# PSU_CLASS_AB.net
KiCad netlist of a schematic drawn in EAGLE
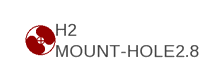
[diagram p0: schematic, sheet 1, part 1 of 2]
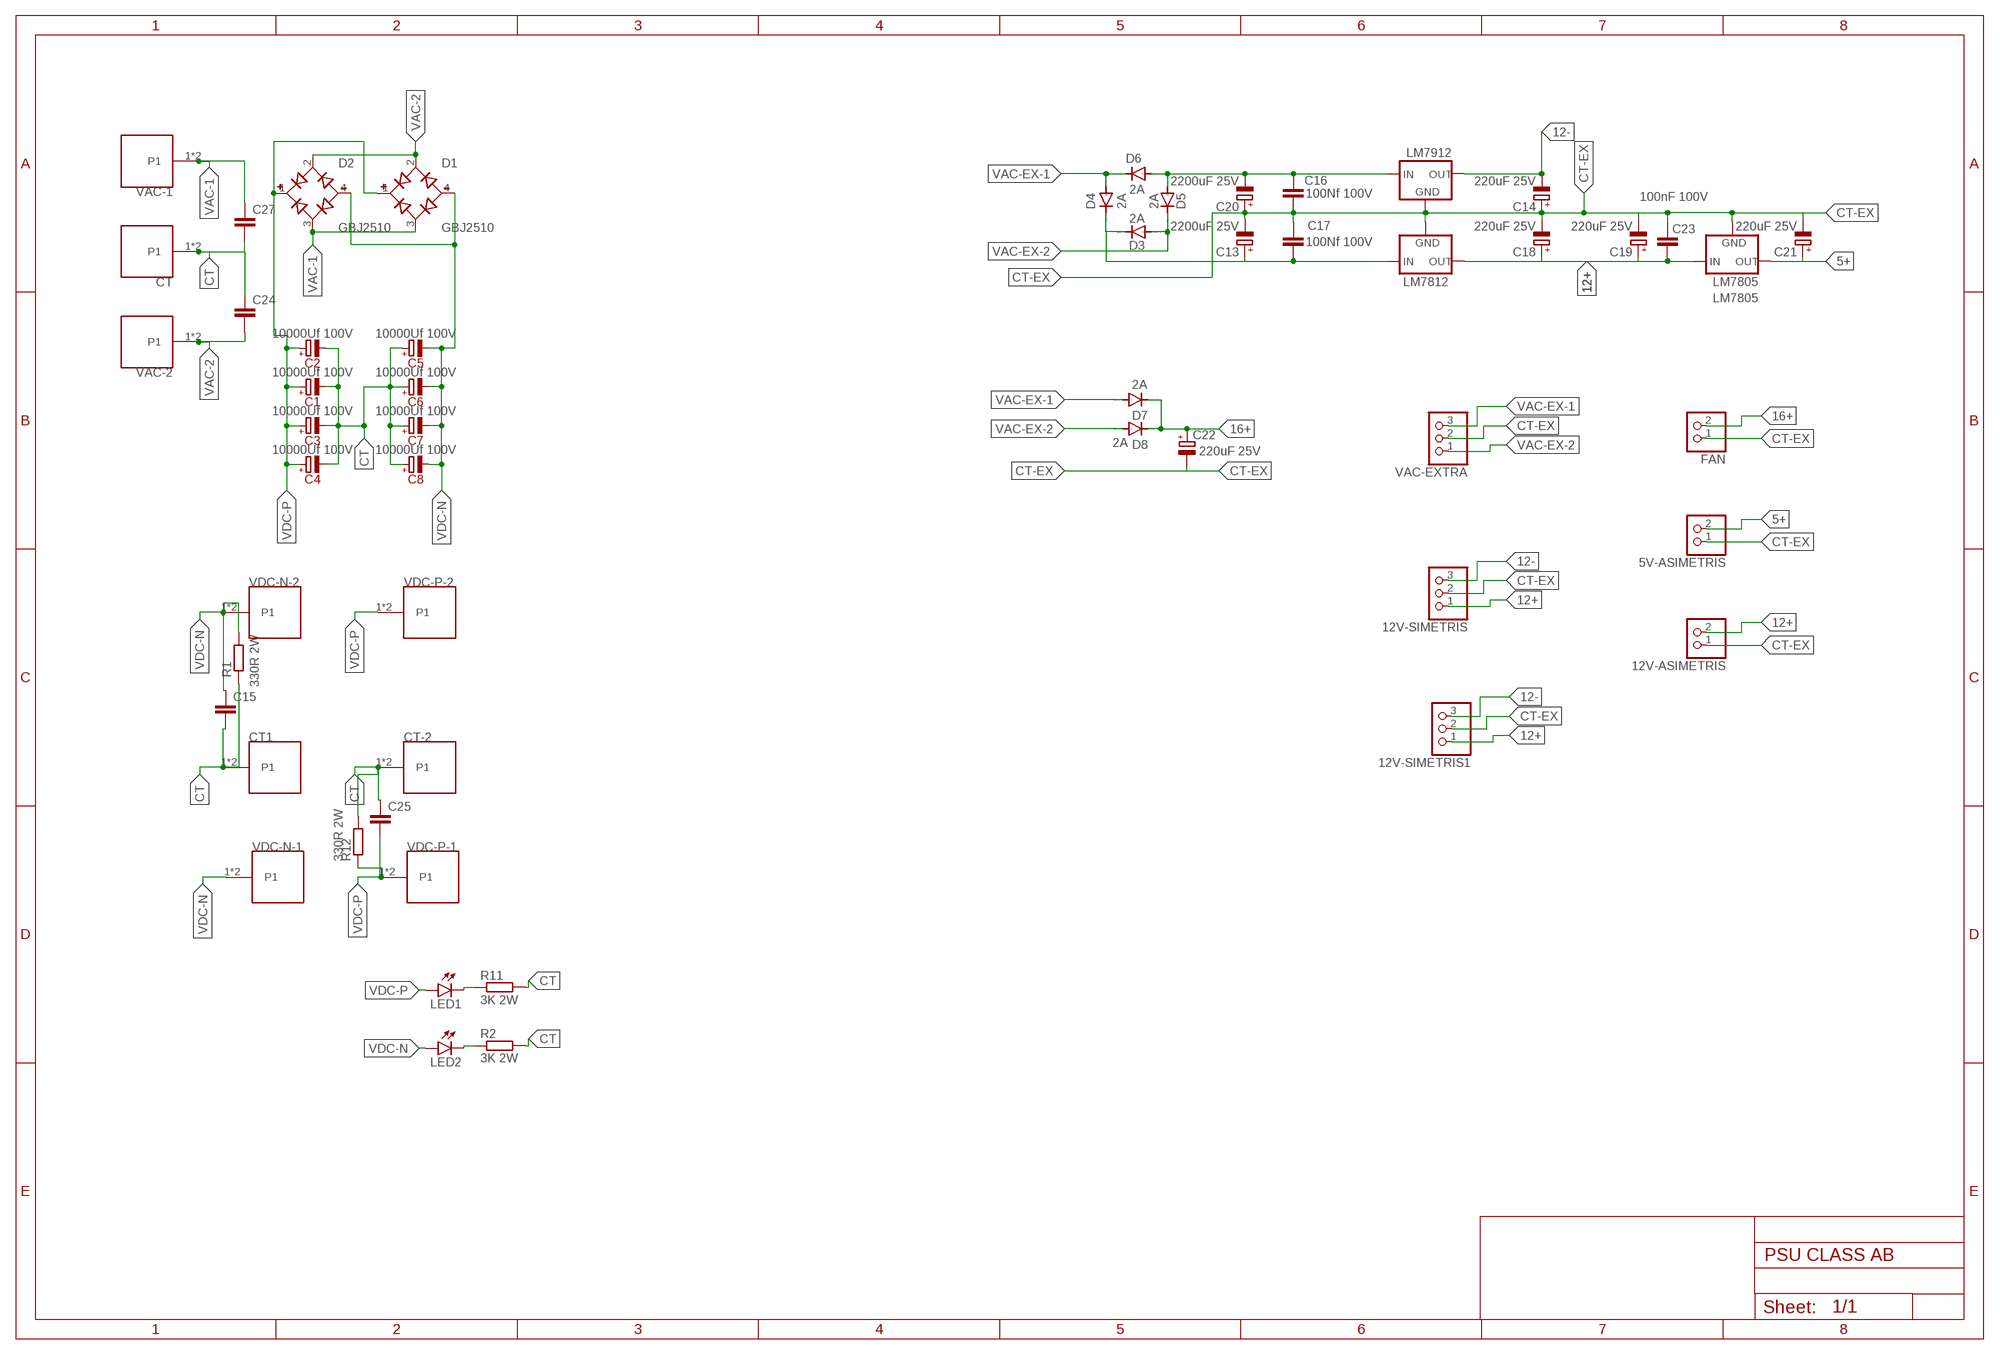
[diagram p1: schematic, sheet 1, part 2 of 2]

(export (version "E")
  (design (tool "Eeschema 10.0.6"))
  (components
    (comp (ref "5V-ASIMETRIS")
      (value "PINHD-1X2")
      (footprint "eagle-import:1X02")
      (libsource (lib "eagle-import") (part "PINHD-1X2"))
    )
    (comp (ref "12V-ASIMETRIS")
      (value "PINHD-1X2")
      (footprint "eagle-import:1X02")
      (libsource (lib "eagle-import") (part "PINHD-1X2"))
    )
    (comp (ref "12V-SIMETRIS")
      (value "PINHD-1X3")
      (footprint "eagle-import:1X03")
      (libsource (lib "eagle-import") (part "PINHD-1X3"))
    )
    (comp (ref "12V-SIMETRIS1")
      (value "PINHD-1X3")
      (footprint "eagle-import:1X03")
      (libsource (lib "eagle-import") (part "PINHD-1X3"))
    )
    (comp (ref "C1")
      (value "10000Uf 100V")
      (footprint "eagle-import:E1,5-4")
      (libsource (lib "eagle-import") (part "?1U/50V"))
    )
    (comp (ref "C2")
      (value "10000Uf 100V")
      (footprint "eagle-import:E1,5-4")
      (libsource (lib "eagle-import") (part "?1U/50V"))
    )
    (comp (ref "C3")
      (value "10000Uf 100V")
      (footprint "eagle-import:E1,5-4")
      (libsource (lib "eagle-import") (part "?1U/50V"))
    )
    (comp (ref "C4")
      (value "10000Uf 100V")
      (footprint "eagle-import:E1,5-4")
      (libsource (lib "eagle-import") (part "?1U/50V"))
    )
    (comp (ref "C5")
      (value "10000Uf 100V")
      (footprint "eagle-import:E1,5-4")
      (libsource (lib "eagle-import") (part "?1U/50V"))
    )
    (comp (ref "C6")
      (value "10000Uf 100V")
      (footprint "eagle-import:E1,5-4")
      (libsource (lib "eagle-import") (part "?1U/50V"))
    )
    (comp (ref "C7")
      (value "10000Uf 100V")
      (footprint "eagle-import:E1,5-4")
      (libsource (lib "eagle-import") (part "?1U/50V"))
    )
    (comp (ref "C8")
      (value "10000Uf 100V")
      (footprint "eagle-import:E1,5-4")
      (libsource (lib "eagle-import") (part "?1U/50V"))
    )
    (comp (ref "C13")
      (value "2200uF 25V")
      (footprint "eagle-import:E3,5-8")
      (libsource (lib "eagle-import") (part "CPOL-EUE3.5-8"))
    )
    (comp (ref "C14")
      (value "220uF 25V")
      (footprint "eagle-import:E3,5-8")
      (libsource (lib "eagle-import") (part "CPOL-EUE3.5-8"))
    )
    (comp (ref "C15")
      (value "C10/5")
      (footprint "eagle-import:C10B5")
      (libsource (lib "eagle-import") (part "capacitor-wima_116_C10/5"))
    )
    (comp (ref "C16")
      (value "100Nf 100V")
      (footprint "eagle-import:C5B3")
      (libsource (lib "eagle-import") (part "C5/3"))
    )
    (comp (ref "C17")
      (value "100Nf 100V")
      (footprint "eagle-import:C5B3")
      (libsource (lib "eagle-import") (part "C5/3"))
    )
    (comp (ref "C18")
      (value "220uF 25V")
      (footprint "eagle-import:E3,5-8")
      (libsource (lib "eagle-import") (part "CPOL-EUE3.5-8"))
    )
    (comp (ref "C19")
      (value "220uF 25V")
      (footprint "eagle-import:E3,5-8")
      (libsource (lib "eagle-import") (part "CPOL-EUE3.5-8"))
    )
    (comp (ref "C20")
      (value "2200uF 25V")
      (footprint "eagle-import:E3,5-8")
      (libsource (lib "eagle-import") (part "CPOL-EUE3.5-8"))
    )
    (comp (ref "C21")
      (value "220uF 25V")
      (footprint "eagle-import:E3,5-8")
      (libsource (lib "eagle-import") (part "CPOL-EUE3.5-8"))
    )
    (comp (ref "C22")
      (value "220uF 25V")
      (footprint "eagle-import:E3,5-8")
      (libsource (lib "eagle-import") (part "CPOL-EUE3.5-8"))
    )
    (comp (ref "C23")
      (value "100nF 100V")
      (footprint "eagle-import:C5B3")
      (libsource (lib "eagle-import") (part "C5/3"))
    )
    (comp (ref "C24")
      (value "C10/5")
      (footprint "eagle-import:C10B5")
      (libsource (lib "eagle-import") (part "capacitor-wima_116_C10/5"))
    )
    (comp (ref "C25")
      (value "C10/5")
      (footprint "eagle-import:C10B5")
      (libsource (lib "eagle-import") (part "capacitor-wima_116_C10/5"))
    )
    (comp (ref "C27")
      (value "C10/5")
      (footprint "eagle-import:C10B5")
      (libsource (lib "eagle-import") (part "capacitor-wima_116_C10/5"))
    )
    (comp (ref "CT")
      (value "62409-1")
      (footprint "eagle-import:TE_62409-1")
      (fields (field (name "MF") "TE Connectivity"))
      (libsource (lib "eagle-import") (part "62409-1"))
    )
    (comp (ref "CT-2")
      (value "62409-1")
      (footprint "eagle-import:TE_62409-1")
      (fields (field (name "MF") "TE Connectivity"))
      (libsource (lib "eagle-import") (part "62409-1"))
    )
    (comp (ref "CT1")
      (value "62409-1")
      (footprint "eagle-import:TE_62409-1")
      (fields (field (name "MF") "TE Connectivity"))
      (libsource (lib "eagle-import") (part "62409-1"))
    )
    (comp (ref "D1")
      (value "GBJ2510")
      (footprint "eagle-import:DIOB_GBJ2510")
      (fields (field (name "MF") "Diodes Inc."))
      (libsource (lib "eagle-import") (part "GBJ2510"))
    )
    (comp (ref "D2")
      (value "GBJ2510")
      (footprint "eagle-import:DIOB_GBJ2510")
      (fields (field (name "MF") "Diodes Inc."))
      (libsource (lib "eagle-import") (part "GBJ2510"))
    )
    (comp (ref "D3")
      (value "2A")
      (footprint "eagle-import:DO41-10")
      (libsource (lib "eagle-import") (part "1N4933"))
    )
    (comp (ref "D4")
      (value "2A")
      (footprint "eagle-import:DO41-10")
      (libsource (lib "eagle-import") (part "1N4933"))
    )
    (comp (ref "D5")
      (value "2A")
      (footprint "eagle-import:DO41-10")
      (libsource (lib "eagle-import") (part "1N4933"))
    )
    (comp (ref "D6")
      (value "2A")
      (footprint "eagle-import:DO41-10")
      (libsource (lib "eagle-import") (part "1N4933"))
    )
    (comp (ref "D7")
      (value "2A")
      (footprint "eagle-import:DO41-10")
      (libsource (lib "eagle-import") (part "1N4933"))
    )
    (comp (ref "D8")
      (value "2A")
      (footprint "eagle-import:DO41-10")
      (libsource (lib "eagle-import") (part "1N4933"))
    )
    (comp (ref "FAN")
      (value "PINHD-1X2")
      (footprint "eagle-import:1X02")
      (libsource (lib "eagle-import") (part "PINHD-1X2"))
    )
    (comp (ref "H2")
      (value "MOUNT-HOLE2.8")
      (footprint "eagle-import:2,8")
      (libsource (lib "eagle-import") (part "MOUNT-HOLE2.8"))
    )
    (comp (ref "LED1")
      (value "LED3MM")
      (footprint "eagle-import:LED3MM")
      (libsource (lib "eagle-import") (part "LED3MM"))
    )
    (comp (ref "LED2")
      (value "LED3MM")
      (footprint "eagle-import:LED3MM")
      (libsource (lib "eagle-import") (part "LED3MM"))
    )
    (comp (ref "LM7805")
      (value "LM7805")
      (footprint "eagle-import:78XXS")
      (libsource (lib "eagle-import") (part "78XXS"))
    )
    (comp (ref "LM7812")
      (value "LM7812")
      (footprint "eagle-import:78XXS")
      (libsource (lib "eagle-import") (part "78XXS"))
    )
    (comp (ref "LM7912")
      (value "LM7912")
      (footprint "eagle-import:79XXS")
      (libsource (lib "eagle-import") (part "79XXS"))
    )
    (comp (ref "R1")
      (value "330R 2W")
      (footprint "eagle-import:0207_15")
      (libsource (lib "eagle-import") (part "R-EU_0207/15"))
    )
    (comp (ref "R2")
      (value "3K 2W")
      (footprint "eagle-import:0207_15")
      (libsource (lib "eagle-import") (part "R-EU_0207/15"))
    )
    (comp (ref "R11")
      (value "3K 2W")
      (footprint "eagle-import:0207_15")
      (libsource (lib "eagle-import") (part "R-EU_0207/15"))
    )
    (comp (ref "R12")
      (value "330R 2W")
      (footprint "eagle-import:0207_15")
      (libsource (lib "eagle-import") (part "R-EU_0207/15"))
    )
    (comp (ref "VAC-1")
      (value "62409-1")
      (footprint "eagle-import:TE_62409-1")
      (fields (field (name "MF") "TE Connectivity"))
      (libsource (lib "eagle-import") (part "62409-1"))
    )
    (comp (ref "VAC-2")
      (value "62409-1")
      (footprint "eagle-import:TE_62409-1")
      (fields (field (name "MF") "TE Connectivity"))
      (libsource (lib "eagle-import") (part "62409-1"))
    )
    (comp (ref "VAC-EXTRA")
      (value "PINHD-1X3")
      (footprint "eagle-import:1X03")
      (libsource (lib "eagle-import") (part "PINHD-1X3"))
    )
    (comp (ref "VDC-N-1")
      (value "62409-1")
      (footprint "eagle-import:TE_62409-1")
      (fields (field (name "MF") "TE Connectivity"))
      (libsource (lib "eagle-import") (part "62409-1"))
    )
    (comp (ref "VDC-N-2")
      (value "62409-1")
      (footprint "eagle-import:TE_62409-1")
      (fields (field (name "MF") "TE Connectivity"))
      (libsource (lib "eagle-import") (part "62409-1"))
    )
    (comp (ref "VDC-P-1")
      (value "62409-1")
      (footprint "eagle-import:TE_62409-1")
      (fields (field (name "MF") "TE Connectivity"))
      (libsource (lib "eagle-import") (part "62409-1"))
    )
    (comp (ref "VDC-P-2")
      (value "62409-1")
      (footprint "eagle-import:TE_62409-1")
      (fields (field (name "MF") "TE Connectivity"))
      (libsource (lib "eagle-import") (part "62409-1"))
    )
  )
  (nets
    (net (code "1") (name "5+") (class "Default")
      (node (ref "5V-ASIMETRIS") (pin "2") (pinfunction "2_2") (pintype "passive"))
      (node (ref "C21") (pin "+") (pinfunction "+_+") (pintype "passive"))
      (node (ref "LM7805") (pin "OUT") (pinfunction "OUT_OUT") (pintype "passive"))
    )
    (net (code "2") (name "12+") (class "Default")
      (node (ref "12V-ASIMETRIS") (pin "2") (pinfunction "2_2") (pintype "passive"))
      (node (ref "12V-SIMETRIS") (pin "1") (pinfunction "1_1") (pintype "passive"))
      (node (ref "12V-SIMETRIS1") (pin "1") (pinfunction "1_1") (pintype "passive"))
      (node (ref "C18") (pin "+") (pinfunction "+_+") (pintype "passive"))
      (node (ref "C19") (pin "+") (pinfunction "+_+") (pintype "passive"))
      (node (ref "C23") (pin "1") (pinfunction "1_1") (pintype "passive"))
      (node (ref "LM7805") (pin "IN") (pinfunction "IN_IN") (pintype "input"))
      (node (ref "LM7812") (pin "OUT") (pinfunction "OUT_OUT") (pintype "passive"))
    )
    (net (code "3") (name "12-") (class "Default")
      (node (ref "12V-SIMETRIS") (pin "3") (pinfunction "3_3") (pintype "passive"))
      (node (ref "12V-SIMETRIS1") (pin "3") (pinfunction "3_3") (pintype "passive"))
      (node (ref "C14") (pin "-") (pinfunction "-_-") (pintype "passive"))
      (node (ref "LM7912") (pin "OUT") (pinfunction "OUT_OUT") (pintype "passive"))
    )
    (net (code "4") (name "16+") (class "Default")
      (node (ref "C22") (pin "+") (pinfunction "+_+") (pintype "passive"))
      (node (ref "D7") (pin "C") (pinfunction "C_C") (pintype "passive"))
      (node (ref "D8") (pin "C") (pinfunction "C_C") (pintype "passive"))
      (node (ref "FAN") (pin "2") (pinfunction "2_2") (pintype "passive"))
    )
    (net (code "5") (name "CT") (class "Default")
      (node (ref "C1") (pin "-") (pinfunction "-_-") (pintype "passive"))
      (node (ref "C15") (pin "2") (pinfunction "2_2") (pintype "passive"))
      (node (ref "C2") (pin "-") (pinfunction "-_-") (pintype "passive"))
      (node (ref "C24") (pin "1") (pinfunction "1_1") (pintype "passive"))
      (node (ref "C25") (pin "1") (pinfunction "1_1") (pintype "passive"))
      (node (ref "C27") (pin "2") (pinfunction "2_2") (pintype "passive"))
      (node (ref "C3") (pin "-") (pinfunction "-_-") (pintype "passive"))
      (node (ref "C4") (pin "-") (pinfunction "-_-") (pintype "passive"))
      (node (ref "C5") (pin "+") (pinfunction "+_+") (pintype "passive"))
      (node (ref "C6") (pin "+") (pinfunction "+_+") (pintype "passive"))
      (node (ref "C7") (pin "+") (pinfunction "+_+") (pintype "passive"))
      (node (ref "C8") (pin "+") (pinfunction "+_+") (pintype "passive"))
      (node (ref "CT") (pin "1") (pinfunction "P1_1") (pintype "passive"))
      (node (ref "CT") (pin "2") (pinfunction "P1_2") (pintype "passive"))
      (node (ref "CT-2") (pin "1") (pinfunction "P1_1") (pintype "passive"))
      (node (ref "CT-2") (pin "2") (pinfunction "P1_2") (pintype "passive"))
      (node (ref "CT1") (pin "1") (pinfunction "P1_1") (pintype "passive"))
      (node (ref "CT1") (pin "2") (pinfunction "P1_2") (pintype "passive"))
      (node (ref "R1") (pin "1") (pinfunction "1_1") (pintype "passive"))
      (node (ref "R11") (pin "2") (pinfunction "2_2") (pintype "passive"))
      (node (ref "R12") (pin "2") (pinfunction "2_2") (pintype "passive"))
      (node (ref "R2") (pin "2") (pinfunction "2_2") (pintype "passive"))
    )
    (net (code "6") (name "CT-EX") (class "Default")
      (node (ref "12V-ASIMETRIS") (pin "1") (pinfunction "1_1") (pintype "passive"))
      (node (ref "12V-SIMETRIS") (pin "2") (pinfunction "2_2") (pintype "passive"))
      (node (ref "12V-SIMETRIS1") (pin "2") (pinfunction "2_2") (pintype "passive"))
      (node (ref "5V-ASIMETRIS") (pin "1") (pinfunction "1_1") (pintype "passive"))
      (node (ref "C13") (pin "-") (pinfunction "-_-") (pintype "passive"))
      (node (ref "C14") (pin "+") (pinfunction "+_+") (pintype "passive"))
      (node (ref "C16") (pin "1") (pinfunction "1_1") (pintype "passive"))
      (node (ref "C17") (pin "2") (pinfunction "2_2") (pintype "passive"))
      (node (ref "C18") (pin "-") (pinfunction "-_-") (pintype "passive"))
      (node (ref "C19") (pin "-") (pinfunction "-_-") (pintype "passive"))
      (node (ref "C20") (pin "+") (pinfunction "+_+") (pintype "passive"))
      (node (ref "C21") (pin "-") (pinfunction "-_-") (pintype "passive"))
      (node (ref "C22") (pin "-") (pinfunction "-_-") (pintype "passive"))
      (node (ref "C23") (pin "2") (pinfunction "2_2") (pintype "passive"))
      (node (ref "FAN") (pin "1") (pinfunction "1_1") (pintype "passive"))
      (node (ref "LM7805") (pin "GND") (pinfunction "GND_GND") (pintype "input"))
      (node (ref "LM7812") (pin "GND") (pinfunction "GND_GND") (pintype "input"))
      (node (ref "LM7912") (pin "GND") (pinfunction "GND_GND") (pintype "input"))
      (node (ref "VAC-EXTRA") (pin "2") (pinfunction "2_2") (pintype "passive"))
    )
    (net (code "7") (name "Net-(C13-Pad+)") (class "Default")
      (node (ref "C13") (pin "+") (pinfunction "+_+") (pintype "passive"))
      (node (ref "C17") (pin "1") (pinfunction "1_1") (pintype "passive"))
      (node (ref "D3") (pin "C") (pinfunction "C_C") (pintype "passive"))
      (node (ref "D4") (pin "C") (pinfunction "C_C") (pintype "passive"))
      (node (ref "LM7812") (pin "IN") (pinfunction "IN_IN") (pintype "input"))
    )
    (net (code "8") (name "Net-(C16-Pad2)") (class "Default")
      (node (ref "C16") (pin "2") (pinfunction "2_2") (pintype "passive"))
      (node (ref "C20") (pin "-") (pinfunction "-_-") (pintype "passive"))
      (node (ref "D5") (pin "A") (pinfunction "A_A") (pintype "passive"))
      (node (ref "D6") (pin "A") (pinfunction "A_A") (pintype "passive"))
      (node (ref "LM7912") (pin "IN") (pinfunction "IN_IN") (pintype "input"))
    )
    (net (code "9") (name "Net-(LED1-C)") (class "Default")
      (node (ref "LED1") (pin "K") (pinfunction "C_K") (pintype "passive"))
      (node (ref "R11") (pin "1") (pinfunction "1_1") (pintype "passive"))
    )
    (net (code "10") (name "Net-(LED2-C)") (class "Default")
      (node (ref "LED2") (pin "K") (pinfunction "C_K") (pintype "passive"))
      (node (ref "R2") (pin "1") (pinfunction "1_1") (pintype "passive"))
    )
    (net (code "11") (name "VAC-1") (class "Default")
      (node (ref "C27") (pin "1") (pinfunction "1_1") (pintype "passive"))
      (node (ref "D1") (pin "3") (pinfunction "AC2_3") (pintype "passive"))
      (node (ref "D2") (pin "3") (pinfunction "AC2_3") (pintype "passive"))
      (node (ref "VAC-1") (pin "1") (pinfunction "P1_1") (pintype "passive"))
      (node (ref "VAC-1") (pin "2") (pinfunction "P1_2") (pintype "passive"))
    )
    (net (code "12") (name "VAC-2") (class "Default")
      (node (ref "C24") (pin "2") (pinfunction "2_2") (pintype "passive"))
      (node (ref "D1") (pin "2") (pinfunction "AC1_2") (pintype "passive"))
      (node (ref "D2") (pin "2") (pinfunction "AC1_2") (pintype "passive"))
      (node (ref "VAC-2") (pin "1") (pinfunction "P1_1") (pintype "passive"))
      (node (ref "VAC-2") (pin "2") (pinfunction "P1_2") (pintype "passive"))
    )
    (net (code "13") (name "VAC-EX-1") (class "Default")
      (node (ref "D4") (pin "A") (pinfunction "A_A") (pintype "passive"))
      (node (ref "D6") (pin "C") (pinfunction "C_C") (pintype "passive"))
      (node (ref "D7") (pin "A") (pinfunction "A_A") (pintype "passive"))
      (node (ref "VAC-EXTRA") (pin "3") (pinfunction "3_3") (pintype "passive"))
    )
    (net (code "14") (name "VAC-EX-2") (class "Default")
      (node (ref "D3") (pin "A") (pinfunction "A_A") (pintype "passive"))
      (node (ref "D5") (pin "C") (pinfunction "C_C") (pintype "passive"))
      (node (ref "D8") (pin "A") (pinfunction "A_A") (pintype "passive"))
      (node (ref "VAC-EXTRA") (pin "1") (pinfunction "1_1") (pintype "passive"))
    )
    (net (code "15") (name "VDC-N") (class "Default")
      (node (ref "C15") (pin "1") (pinfunction "1_1") (pintype "passive"))
      (node (ref "C5") (pin "-") (pinfunction "-_-") (pintype "passive"))
      (node (ref "C6") (pin "-") (pinfunction "-_-") (pintype "passive"))
      (node (ref "C7") (pin "-") (pinfunction "-_-") (pintype "passive"))
      (node (ref "C8") (pin "-") (pinfunction "-_-") (pintype "passive"))
      (node (ref "D1") (pin "4") (pinfunction "-_4") (pintype "passive"))
      (node (ref "D2") (pin "4") (pinfunction "-_4") (pintype "passive"))
      (node (ref "LED2") (pin "A") (pinfunction "A_A") (pintype "passive"))
      (node (ref "R1") (pin "2") (pinfunction "2_2") (pintype "passive"))
      (node (ref "VDC-N-1") (pin "1") (pinfunction "P1_1") (pintype "passive"))
      (node (ref "VDC-N-1") (pin "2") (pinfunction "P1_2") (pintype "passive"))
      (node (ref "VDC-N-2") (pin "1") (pinfunction "P1_1") (pintype "passive"))
      (node (ref "VDC-N-2") (pin "2") (pinfunction "P1_2") (pintype "passive"))
    )
    (net (code "16") (name "VDC-P") (class "Default")
      (node (ref "C1") (pin "+") (pinfunction "+_+") (pintype "passive"))
      (node (ref "C2") (pin "+") (pinfunction "+_+") (pintype "passive"))
      (node (ref "C25") (pin "2") (pinfunction "2_2") (pintype "passive"))
      (node (ref "C3") (pin "+") (pinfunction "+_+") (pintype "passive"))
      (node (ref "C4") (pin "+") (pinfunction "+_+") (pintype "passive"))
      (node (ref "D1") (pin "1") (pinfunction "+_1") (pintype "passive"))
      (node (ref "D2") (pin "1") (pinfunction "+_1") (pintype "passive"))
      (node (ref "LED1") (pin "A") (pinfunction "A_A") (pintype "passive"))
      (node (ref "R12") (pin "1") (pinfunction "1_1") (pintype "passive"))
      (node (ref "VDC-P-1") (pin "1") (pinfunction "P1_1") (pintype "passive"))
      (node (ref "VDC-P-1") (pin "2") (pinfunction "P1_2") (pintype "passive"))
      (node (ref "VDC-P-2") (pin "1") (pinfunction "P1_1") (pintype "passive"))
      (node (ref "VDC-P-2") (pin "2") (pinfunction "P1_2") (pintype "passive"))
    )
  )
)
